# Motion_Sensor.net
KiCad netlist of a schematic drawn in Altium Designer
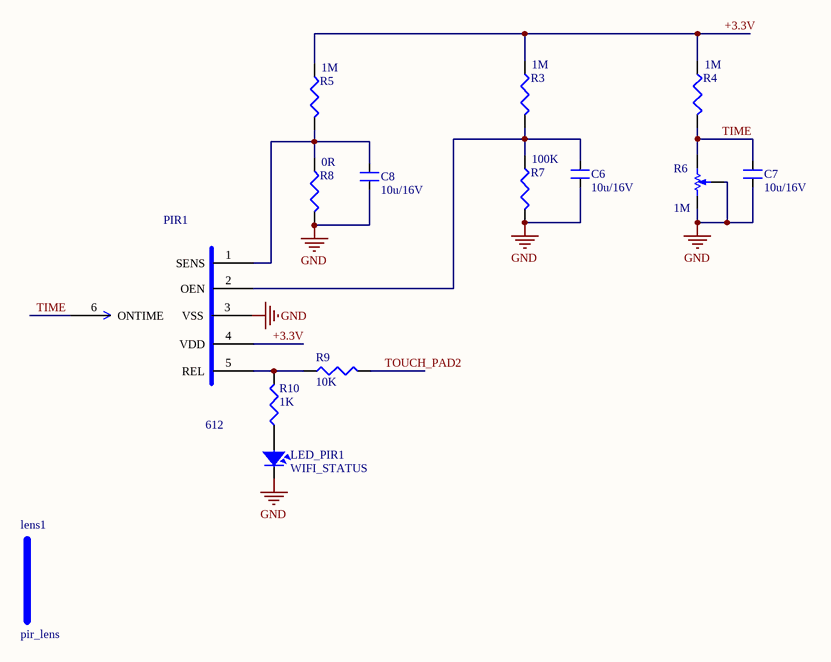
[diagram p0: Motion_Sensor.SchDoc]

(export (version "E")
  (design (tool "Eeschema 10.0.6"))
  (components
    (comp (ref "C6")
      (value "10u/16V")
      (footprint "SM-0805")
      (description "Cap SMD")
      (libsource (lib "syhaunguyen") (part "CM"))
    )
    (comp (ref "C7")
      (value "10u/16V")
      (footprint "SM-0805")
      (description "Cap SMD")
      (libsource (lib "syhaunguyen") (part "CM"))
    )
    (comp (ref "C8")
      (value "10u/16V")
      (footprint "SM-0805")
      (description "Cap SMD")
      (libsource (lib "syhaunguyen") (part "CM"))
    )
    (comp (ref "LED_PIR1")
      (value "WIFI_STATUS")
      (footprint "R0603")
      (description "LED Single colour Green and Red")
      (libsource (lib "CTT4_HTV") (part "LED"))
    )
    (comp (ref "lens1")
      (value "pir_lens")
      (footprint "PCBComponent_1")
      (libsource (lib "MS") (part "pir_lens"))
    )
    (comp (ref "PIR1") (value "612") (footprint "TO5") (libsource (lib "MS") (part "PIR_612")))
    (comp (ref "R3")
      (value "1M")
      (footprint "J1-0603")
      (description "Resistor")
      (fields (field (name "PUBLISHER") "Altium Limited"))
      (libsource (lib "Miscellaneous Devices") (part "Res3"))
    )
    (comp (ref "R4")
      (value "1M")
      (footprint "J1-0603")
      (description "Resistor")
      (fields (field (name "PUBLISHER") "Altium Limited"))
      (libsource (lib "Miscellaneous Devices") (part "Res3"))
    )
    (comp (ref "R5")
      (value "1M")
      (footprint "J1-0603")
      (description "Resistor")
      (fields (field (name "PUBLISHER") "Altium Limited"))
      (libsource (lib "Miscellaneous Devices") (part "Res3"))
    )
    (comp (ref "R6")
      (value "1M")
      (footprint "POT4MM-2")
      (description "Square Trimming Potentiometer")
      (fields (field (name "PUBLISHER") "Altium Limited"))
      (libsource (lib "Miscellaneous Devices") (part "RPot SM"))
    )
    (comp (ref "R7")
      (value "100K")
      (footprint "J1-0603")
      (description "Resistor")
      (fields (field (name "PUBLISHER") "Altium Limited"))
      (libsource (lib "Miscellaneous Devices") (part "Res3"))
    )
    (comp (ref "R8")
      (value "0R")
      (footprint "J1-0603")
      (description "Resistor")
      (fields (field (name "PUBLISHER") "Altium Limited"))
      (libsource (lib "Miscellaneous Devices") (part "Res3"))
    )
    (comp (ref "R9")
      (value "10K")
      (footprint "J1-0603")
      (description "Resistor")
      (fields (field (name "PUBLISHER") "Altium Limited"))
      (libsource (lib "Miscellaneous Devices") (part "Res3"))
    )
    (comp (ref "R10")
      (value "1K")
      (footprint "J1-0603")
      (description "Resistor")
      (fields (field (name "PUBLISHER") "Altium Limited"))
      (libsource (lib "Miscellaneous Devices") (part "Res3"))
    )
  )
  (nets
    (net (code "1") (name "/+3.3V") (class "Default")
      (node (ref "PIR1") (pin "4") (pinfunction "VDD_4") (pintype "passive"))
      (node (ref "R3") (pin "1") (pinfunction "1_1") (pintype "passive"))
      (node (ref "R4") (pin "1") (pinfunction "1_1") (pintype "passive"))
      (node (ref "R5") (pin "1") (pinfunction "1_1") (pintype "passive"))
    )
    (net (code "2") (name "/TIME") (class "Default")
      (node (ref "C7") (pin "1") (pinfunction "1_1") (pintype "passive"))
      (node (ref "PIR1") (pin "6") (pinfunction "ONTIME_6") (pintype "passive"))
      (node (ref "R4") (pin "2") (pinfunction "2_2") (pintype "passive"))
      (node (ref "R6") (pin "CW") (pinfunction "+_CW") (pintype "passive"))
    )
    (net (code "3") (name "/TOUCH_PAD2") (class "Default")
      (node (ref "R9") (pin "2") (pinfunction "2_2") (pintype "passive"))
    )
    (net (code "4") (name "GND") (class "Default")
      (node (ref "C6") (pin "2") (pinfunction "2_2") (pintype "passive"))
      (node (ref "C7") (pin "2") (pinfunction "2_2") (pintype "passive"))
      (node (ref "C8") (pin "2") (pinfunction "2_2") (pintype "passive"))
      (node (ref "LED_PIR1") (pin "2") (pinfunction "2_2") (pintype "passive"))
      (node (ref "PIR1") (pin "3") (pinfunction "VSS_3") (pintype "passive"))
      (node (ref "R6") (pin "CCW") (pinfunction "-_CCW") (pintype "passive"))
      (node (ref "R6") (pin "W") (pinfunction "W_W") (pintype "passive"))
      (node (ref "R7") (pin "2") (pinfunction "2_2") (pintype "passive"))
      (node (ref "R8") (pin "2") (pinfunction "2_2") (pintype "passive"))
    )
    (net (code "5") (name "Net-(LED_PIR1-Pad1)") (class "Default")
      (node (ref "LED_PIR1") (pin "1") (pinfunction "1_1") (pintype "passive"))
      (node (ref "R10") (pin "1") (pinfunction "1_1") (pintype "passive"))
    )
    (net (code "6") (name "Net-(PIR1-OEN)") (class "Default")
      (node (ref "C6") (pin "1") (pinfunction "1_1") (pintype "passive"))
      (node (ref "PIR1") (pin "2") (pinfunction "OEN_2") (pintype "passive"))
      (node (ref "R3") (pin "2") (pinfunction "2_2") (pintype "passive"))
      (node (ref "R7") (pin "1") (pinfunction "1_1") (pintype "passive"))
    )
    (net (code "7") (name "Net-(PIR1-REL)") (class "Default")
      (node (ref "PIR1") (pin "5") (pinfunction "REL_5") (pintype "passive"))
      (node (ref "R10") (pin "2") (pinfunction "2_2") (pintype "passive"))
      (node (ref "R9") (pin "1") (pinfunction "1_1") (pintype "passive"))
    )
    (net (code "8") (name "Net-(PIR1-SENS)") (class "Default")
      (node (ref "C8") (pin "1") (pinfunction "1_1") (pintype "passive"))
      (node (ref "PIR1") (pin "1") (pinfunction "SENS_1") (pintype "passive"))
      (node (ref "R5") (pin "2") (pinfunction "2_2") (pintype "passive"))
      (node (ref "R8") (pin "1") (pinfunction "1_1") (pintype "passive"))
    )
  )
)
